# 1_P1.net
KiCad netlist of a schematic drawn in Altium Designer
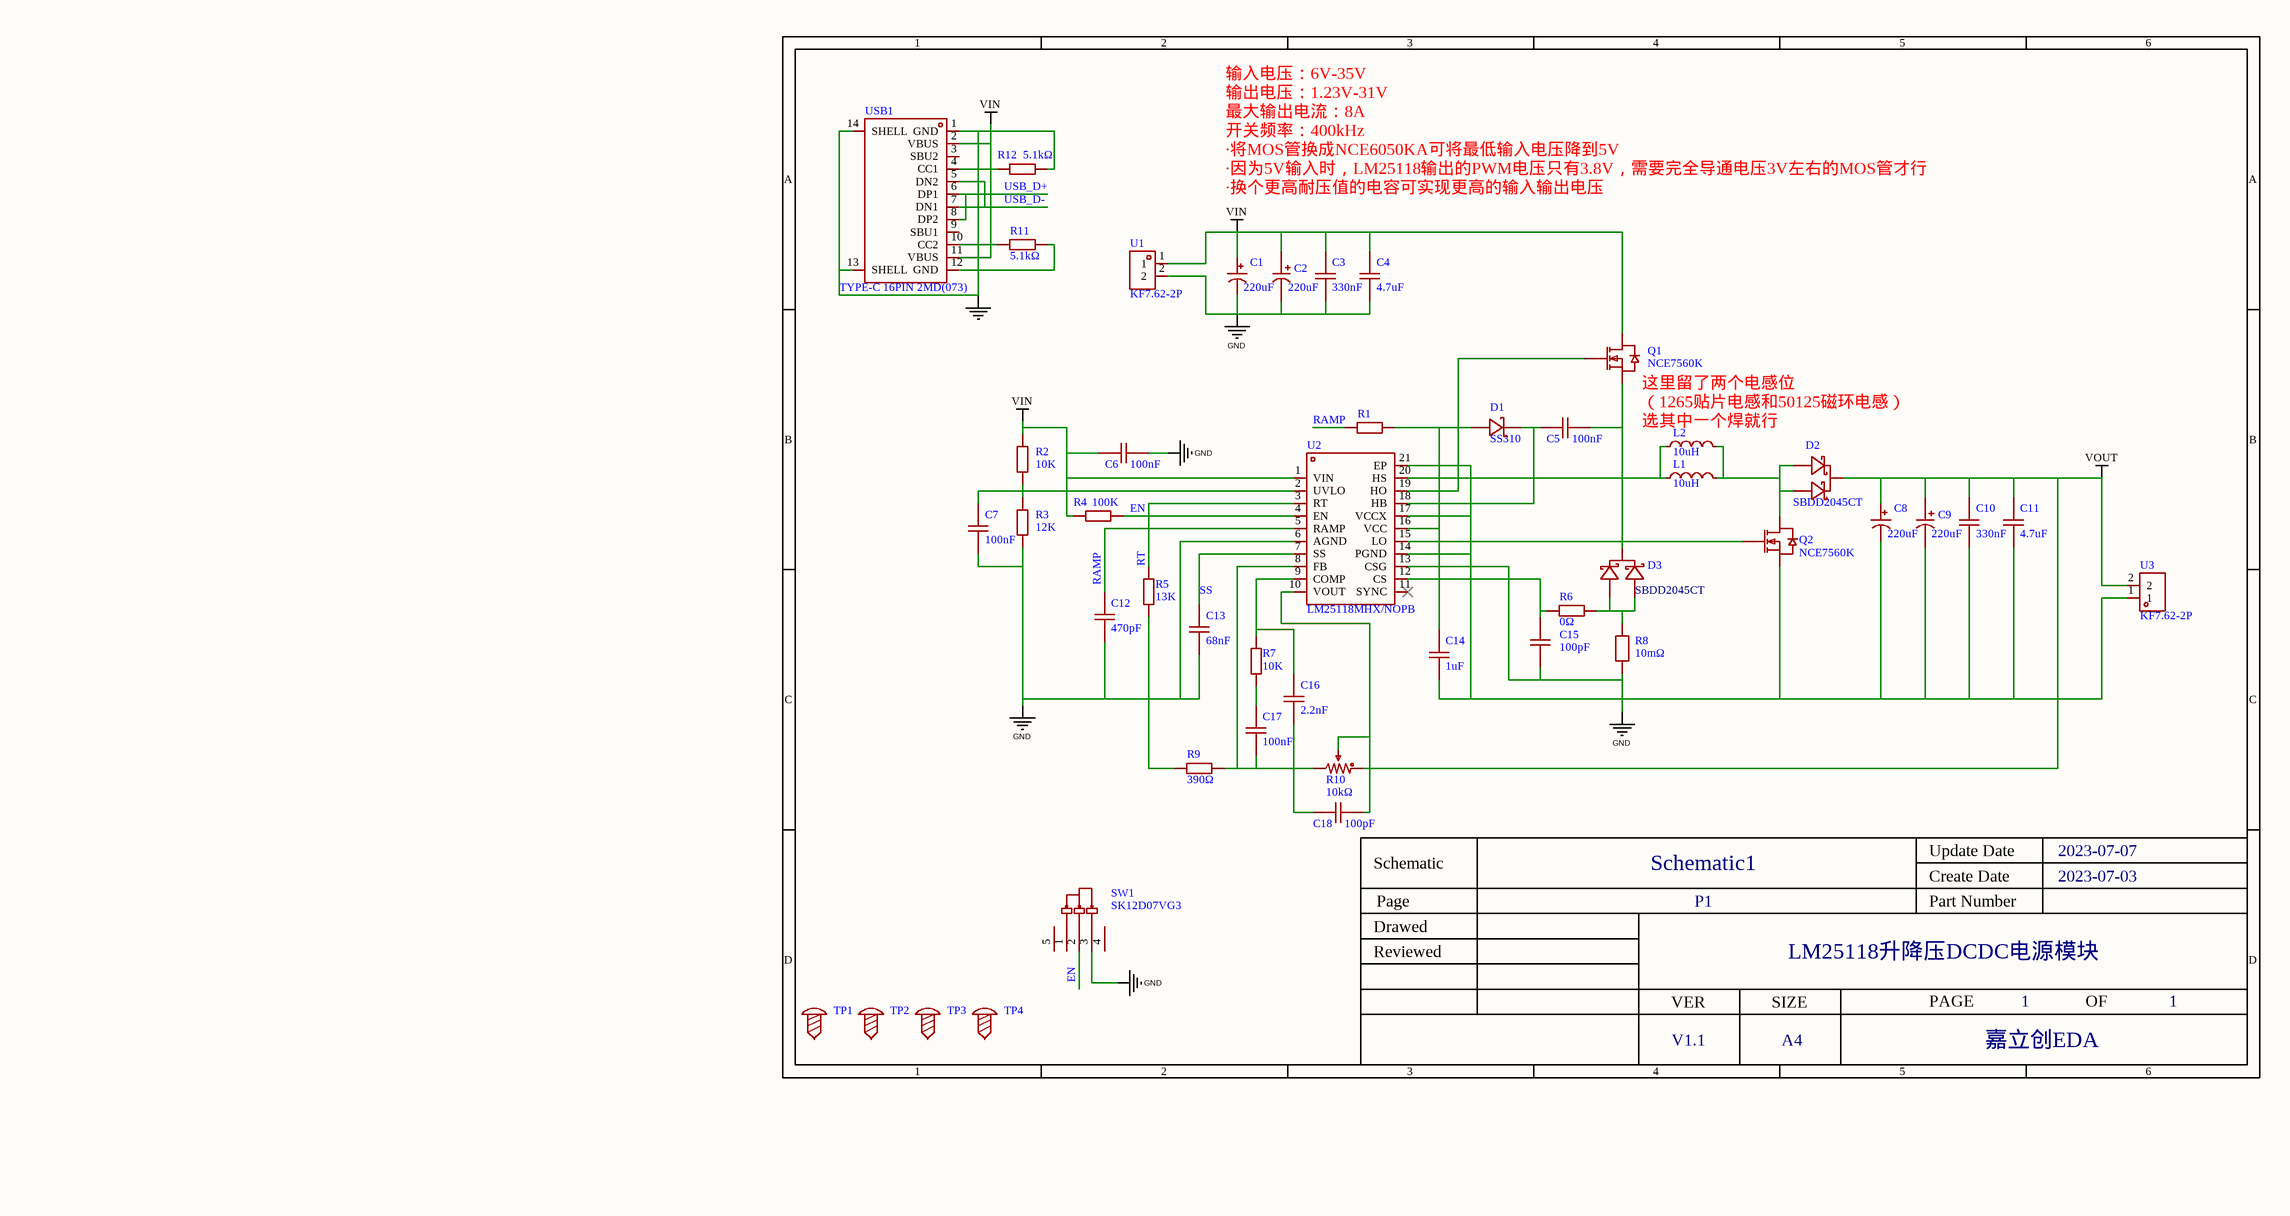
[diagram p0: 1_P1.schdoc]

(export (version "E")
  (design (tool "Eeschema 10.0.6"))
  (components
    (comp (ref "C1")
      (value "220uF")
      (footprint "CAP-TH_BD8.0-P3.50-D0.6-FD")
      (fields
        (field (name "MANUFACTURER") "CX(承兴)")
        (field (name "MANUFACTURER PART") "GR227M035F12RR0VL4FP0")
        (field (name "TOLERANCE") "±20%")
      )
      (libsource (lib "altium-import") (part "root_3_GR227M035F12RR0VL4FP0_"))
    )
    (comp (ref "C2")
      (value "220uF")
      (footprint "CAP-TH_BD8.0-P3.50-D0.6-FD-2")
      (fields
        (field (name "MANUFACTURER") "KNSCHA(科尼盛)")
        (field (name "MANUFACTURER PART") "KNH2220UF35V149EC0049")
        (field (name "TOLERANCE") "±20%")
      )
      (libsource (lib "altium-import") (part "root_3_KNH2220UF35V149EC0049_"))
    )
    (comp (ref "C3")
      (value "330nF")
      (footprint "C0805")
      (libsource (lib "altium-import") (part "root_1_CAP_0805_"))
    )
    (comp (ref "C4")
      (value "4.7uF")
      (footprint "C0805")
      (libsource (lib "altium-import") (part "root_1_CAP_0805_"))
    )
    (comp (ref "C5")
      (value "100nF")
      (footprint "C0805")
      (libsource (lib "altium-import") (part "root_0_CAP_0805_"))
    )
    (comp (ref "C6")
      (value "100nF")
      (footprint "C0805")
      (libsource (lib "altium-import") (part "root_0_CAP_0805_"))
    )
    (comp (ref "C7")
      (value "100nF")
      (footprint "C0805")
      (libsource (lib "altium-import") (part "root_1_CAP_0805_"))
    )
    (comp (ref "C8")
      (value "220uF")
      (footprint "CAP-TH_BD8.0-P3.50-D0.6-FD")
      (fields
        (field (name "MANUFACTURER") "CX(承兴)")
        (field (name "MANUFACTURER PART") "GR227M035F12RR0VL4FP0")
        (field (name "TOLERANCE") "±20%")
      )
      (libsource (lib "altium-import") (part "root_3_GR227M035F12RR0VL4FP0_"))
    )
    (comp (ref "C9")
      (value "220uF")
      (footprint "CAP-TH_BD8.0-P3.50-D0.6-FD-2")
      (fields
        (field (name "MANUFACTURER") "KNSCHA(科尼盛)")
        (field (name "MANUFACTURER PART") "KNH2220UF35V149EC0049")
        (field (name "TOLERANCE") "±20%")
      )
      (libsource (lib "altium-import") (part "root_3_KNH2220UF35V149EC0049_"))
    )
    (comp (ref "C10")
      (value "330nF")
      (footprint "C0805")
      (libsource (lib "altium-import") (part "root_1_CAP_0805_"))
    )
    (comp (ref "C11")
      (value "4.7uF")
      (footprint "C0805")
      (libsource (lib "altium-import") (part "root_1_CAP_0805_"))
    )
    (comp (ref "C12")
      (value "470pF")
      (footprint "C0805")
      (libsource (lib "altium-import") (part "root_1_CAP_0805_"))
    )
    (comp (ref "C13")
      (value "68nF")
      (footprint "C0805")
      (libsource (lib "altium-import") (part "root_1_CAP_0805_"))
    )
    (comp (ref "C14")
      (value "1uF")
      (footprint "C0805")
      (libsource (lib "altium-import") (part "root_1_CAP_0805_"))
    )
    (comp (ref "C15")
      (value "100pF")
      (footprint "C0805")
      (libsource (lib "altium-import") (part "root_1_CAP_0805_"))
    )
    (comp (ref "C16")
      (value "2.2nF")
      (footprint "C0805")
      (libsource (lib "altium-import") (part "root_1_CAP_0805_"))
    )
    (comp (ref "C17")
      (value "100nF")
      (footprint "C0805")
      (libsource (lib "altium-import") (part "root_1_CAP_0805_"))
    )
    (comp (ref "C18")
      (value "100pF")
      (footprint "C0805")
      (libsource (lib "altium-import") (part "root_0_CAP_0805_"))
    )
    (comp (ref "D1")
      (value "SS310")
      (footprint "SMA_L4.3-W2.6-LS5.2-RD")
      (fields (field (name "MANUFACTURER") "MDD"))
      (libsource (lib "altium-import") (part "root_2_SS310_C15874_"))
    )
    (comp (ref "D2")
      (value "SBDD2045CT")
      (footprint "TO-252-2_L6.5-W6.1-P4.58-LS10.0-TL")
      (fields (field (name "MANUFACTURER") "CJ(江苏长电/长晶)"))
      (libsource (lib "altium-import") (part "root_1_SBDD2045CT_"))
    )
    (comp (ref "D3")
      (value "SBDD2045CT")
      (footprint "TO-252-2_L6.5-W6.1-P4.58-LS10.0-TL")
      (fields (field (name "MANUFACTURER") "CJ(江苏长电/长晶)"))
      (libsource (lib "altium-import") (part "root_2_SBDD2045CT_"))
    )
    (comp (ref "L1")
      (value "10uH")
      (footprint "IND-TH_L16.5-W8.5-P11.00-D1.0")
      (fields
        (field (name "MANUFACTURER") "Sunltech(韩国顺磁)")
        (field (name "MANUFACTURER PART") "SLT050125T100MUB")
        (field (name "TOLERANCE") "±20%")
      )
      (libsource (lib "altium-import") (part "root_0_SLT050125T100MUB_"))
    )
    (comp (ref "L2")
      (value "10uH")
      (footprint "IND-SMD_L13.5-W12.6")
      (fields
        (field (name "MANUFACTURER") "XR(祥如)")
        (field (name "MANUFACTURER PART") "XR1265-100M")
        (field (name "TOLERANCE") "±20%")
      )
      (libsource (lib "altium-import") (part "root_0_XR1265-100M_"))
    )
    (comp (ref "Q1")
      (value "NCE7560K")
      (footprint "TO-252-2_L6.6-W6.1-P4.57-LS9.9-TL-CW")
      (fields (field (name "MANUFACTURER") "NCE(无锡新洁能)"))
      (libsource (lib "altium-import") (part "root_0_NCE7560K_"))
    )
    (comp (ref "Q2")
      (value "NCE7560K")
      (footprint "TO-252-2_L6.6-W6.1-P4.57-LS9.9-TL-CW")
      (fields (field (name "MANUFACTURER") "NCE(无锡新洁能)"))
      (libsource (lib "altium-import") (part "root_0_NCE7560K_"))
    )
    (comp (ref "R1")
      (value "100K")
      (footprint "R0805")
      (libsource (lib "altium-import") (part "root_0_Res_0805_"))
    )
    (comp (ref "R2")
      (value "10K")
      (footprint "R0805")
      (libsource (lib "altium-import") (part "root_1_Res_0805_"))
    )
    (comp (ref "R3")
      (value "12K")
      (footprint "R0805")
      (libsource (lib "altium-import") (part "root_1_Res_0805_"))
    )
    (comp (ref "R4")
      (value "100K")
      (footprint "R0805")
      (libsource (lib "altium-import") (part "root_0_Res_0805_"))
    )
    (comp (ref "R5")
      (value "13K")
      (footprint "R0805")
      (libsource (lib "altium-import") (part "root_1_Res_0805_"))
    )
    (comp (ref "R6")
      (value "0Ω")
      (footprint "R0805")
      (libsource (lib "altium-import") (part "root_0_Res_0805_"))
    )
    (comp (ref "R7")
      (value "10K")
      (footprint "R0805")
      (libsource (lib "altium-import") (part "root_1_Res_0805_"))
    )
    (comp (ref "R8")
      (value "10mΩ")
      (footprint "RES-SMD_L6.4-W3.2-R2512")
      (fields
        (field (name "MANUFACTURER") "Milliohm(毫欧)")
        (field (name "MANUFACTURER PART") "HoJLR2512-3W-10mR-1%")
      )
      (libsource (lib "altium-import") (part "root_1_HoJLR2512-3W-10mR-1%_"))
    )
    (comp (ref "R9")
      (value "390Ω")
      (footprint "R0805")
      (libsource (lib "altium-import") (part "root_0_Res_0805_"))
    )
    (comp (ref "R10")
      (value "10kΩ")
      (footprint "RES-ADJ-TH_3P-L10.0-W10.0-P2.50-L")
      (fields
        (field (name "MANUFACTURER") "BOCHEN(博晨)")
        (field (name "MANUFACTURER PART") "3296W-1-103")
        (field (name "TOLERANCE") "±10%")
      )
      (libsource (lib "altium-import") (part "root_0_3296W-1-103_"))
    )
    (comp (ref "R11")
      (value "5.1kΩ")
      (footprint "R0805")
      (fields
        (field (name "MANUFACTURER") "UNI-ROYAL(厚声)")
        (field (name "MANUFACTURER PART") "0805W8F5101T5E")
        (field (name "TOLERANCE") "±1%")
      )
      (libsource (lib "altium-import") (part "root_0_0805W8F5101T5E_"))
    )
    (comp (ref "R12")
      (value "5.1kΩ")
      (footprint "R0805")
      (fields
        (field (name "MANUFACTURER") "UNI-ROYAL(厚声)")
        (field (name "MANUFACTURER PART") "0805W8F5101T5E")
        (field (name "TOLERANCE") "±1%")
      )
      (libsource (lib "altium-import") (part "root_0_0805W8F5101T5E_"))
    )
    (comp (ref "SW1")
      (value "SK12D07VG3")
      (footprint "SW-TH_SK12D07VG3")
      (fields (field (name "MANUFACTURER") "SHOU HAN(首韩)"))
      (libsource (lib "altium-import") (part "root_0_SK12D07VG3_"))
    )
    (comp (ref "TP1") (value "~") (footprint "M3螺丝") (libsource (lib "altium-import") (part "root_0_M3螺丝_")))
    (comp (ref "TP2") (value "~") (footprint "M3螺丝") (libsource (lib "altium-import") (part "root_0_M3螺丝_")))
    (comp (ref "TP3") (value "~") (footprint "M3螺丝") (libsource (lib "altium-import") (part "root_0_M3螺丝_")))
    (comp (ref "TP4") (value "~") (footprint "M3螺丝") (libsource (lib "altium-import") (part "root_0_M3螺丝_")))
    (comp (ref "U1")
      (value "KF7.62-2P")
      (footprint "CONN-TH_2P-P7.62_KEFA_KF7.62-2P")
      (fields (field (name "MANUFACTURER") "KEFA(科发)"))
      (libsource (lib "altium-import") (part "root_0_mirrored_KF7.62-2P_C5173665_"))
    )
    (comp (ref "U2")
      (value "LM25118MHX/NOPB")
      (footprint "HTSSOP-20_L6.5-W4.4-P0.65-LS6.4-BL-EP")
      (fields (field (name "MANUFACTURER") "TI(德州仪器)"))
      (libsource (lib "altium-import") (part "root_0_LM25118MHX/NOPB_"))
    )
    (comp (ref "U3")
      (value "KF7.62-2P")
      (footprint "CONN-TH_2P-P7.62_KEFA_KF7.62-2P")
      (fields (field (name "MANUFACTURER") "KEFA(科发)"))
      (libsource (lib "altium-import") (part "root_2_mirrored_KF7.62-2P_C5173665_"))
    )
    (comp (ref "USB1")
      (value "TYPE-C 16PIN 2MD(073)")
      (footprint "USB-C-SMD_TYPE-C-6PIN-2MD-073")
      (fields (field (name "MANUFACTURER") "SHOU HAN(首韩)"))
      (libsource (lib "altium-import") (part "root_0_mirrored_TYPE-C 16PIN 2MD(073)_"))
    )
  )
  (nets
    (net (code "1") (name "/EN") (class "Default")
      (node (ref "R4") (pin "2") (pinfunction "2_2") (pintype "passive"))
      (node (ref "SW1") (pin "2") (pinfunction "2_2") (pintype "passive"))
      (node (ref "U2") (pin "4") (pinfunction "EN_4") (pintype "passive"))
    )
    (net (code "2") (name "/RAMP") (class "Default")
      (node (ref "C12") (pin "2") (pinfunction "2_2") (pintype "passive"))
      (node (ref "R1") (pin "1") (pinfunction "1_1") (pintype "passive"))
      (node (ref "U2") (pin "5") (pinfunction "RAMP_5") (pintype "passive"))
    )
    (net (code "3") (name "/RT") (class "Default")
      (node (ref "R5") (pin "2") (pinfunction "2_2") (pintype "passive"))
      (node (ref "U2") (pin "3") (pinfunction "RT_3") (pintype "passive"))
    )
    (net (code "4") (name "/SS") (class "Default")
      (node (ref "C13") (pin "2") (pinfunction "2_2") (pintype "passive"))
      (node (ref "U2") (pin "7") (pinfunction "SS_7") (pintype "passive"))
    )
    (net (code "5") (name "/USB_D+") (class "Default")
      (node (ref "USB1") (pin "6") (pinfunction "DP1_6") (pintype "passive"))
      (node (ref "USB1") (pin "8") (pinfunction "DP2_8") (pintype "passive"))
    )
    (net (code "6") (name "/USB_D-") (class "Default")
      (node (ref "USB1") (pin "5") (pinfunction "DN2_5") (pintype "passive"))
      (node (ref "USB1") (pin "7") (pinfunction "DN1_7") (pintype "passive"))
    )
    (net (code "7") (name "GND") (class "Default")
      (node (ref "C1") (pin "2") (pinfunction "2_2") (pintype "passive"))
      (node (ref "C10") (pin "1") (pinfunction "1_1") (pintype "passive"))
      (node (ref "C11") (pin "1") (pinfunction "1_1") (pintype "passive"))
      (node (ref "C12") (pin "1") (pinfunction "1_1") (pintype "passive"))
      (node (ref "C13") (pin "1") (pinfunction "1_1") (pintype "passive"))
      (node (ref "C14") (pin "1") (pinfunction "1_1") (pintype "passive"))
      (node (ref "C15") (pin "1") (pinfunction "1_1") (pintype "passive"))
      (node (ref "C2") (pin "2") (pinfunction "2_2") (pintype "passive"))
      (node (ref "C3") (pin "1") (pinfunction "1_1") (pintype "passive"))
      (node (ref "C4") (pin "1") (pinfunction "1_1") (pintype "passive"))
      (node (ref "C6") (pin "2") (pinfunction "2_2") (pintype "passive"))
      (node (ref "C7") (pin "1") (pinfunction "1_1") (pintype "passive"))
      (node (ref "C8") (pin "2") (pinfunction "2_2") (pintype "passive"))
      (node (ref "C9") (pin "2") (pinfunction "2_2") (pintype "passive"))
      (node (ref "Q2") (pin "3") (pinfunction "S_3") (pintype "passive"))
      (node (ref "R11") (pin "2") (pinfunction "2_2") (pintype "passive"))
      (node (ref "R12") (pin "2") (pinfunction "2_2") (pintype "passive"))
      (node (ref "R3") (pin "1") (pinfunction "1_1") (pintype "passive"))
      (node (ref "R5") (pin "1") (pinfunction "1_1") (pintype "passive"))
      (node (ref "R8") (pin "1") (pinfunction "1_1") (pintype "passive"))
      (node (ref "R9") (pin "1") (pinfunction "1_1") (pintype "passive"))
      (node (ref "SW1") (pin "3") (pinfunction "3_3") (pintype "passive"))
      (node (ref "U1") (pin "2") (pinfunction "2_2") (pintype "passive"))
      (node (ref "U2") (pin "13") (pinfunction "CSG_13") (pintype "passive"))
      (node (ref "U2") (pin "14") (pinfunction "PGND_14") (pintype "passive"))
      (node (ref "U2") (pin "17") (pinfunction "VCCX_17") (pintype "passive"))
      (node (ref "U2") (pin "21") (pinfunction "EP_21") (pintype "passive"))
      (node (ref "U2") (pin "6") (pinfunction "AGND_6") (pintype "passive"))
      (node (ref "U3") (pin "1") (pinfunction "1_1") (pintype "passive"))
      (node (ref "USB1") (pin "1") (pinfunction "GND_1") (pintype "passive"))
      (node (ref "USB1") (pin "12") (pinfunction "GND_12") (pintype "passive"))
      (node (ref "USB1") (pin "13") (pinfunction "SHELL_13") (pintype "passive"))
      (node (ref "USB1") (pin "14") (pinfunction "SHELL_14") (pintype "passive"))
    )
    (net (code "8") (name "Net-(C17-Pad2)") (class "Default")
      (node (ref "C17") (pin "2") (pinfunction "2_2") (pintype "passive"))
      (node (ref "R7") (pin "1") (pinfunction "1_1") (pintype "passive"))
    )
    (net (code "9") (name "Net-(D1-A)") (class "Default")
      (node (ref "C14") (pin "2") (pinfunction "2_2") (pintype "passive"))
      (node (ref "D1") (pin "2") (pinfunction "A_2") (pintype "passive"))
      (node (ref "R1") (pin "2") (pinfunction "2_2") (pintype "passive"))
      (node (ref "U2") (pin "16") (pinfunction "VCC_16") (pintype "passive"))
    )
    (net (code "10") (name "Net-(D1-K)") (class "Default")
      (node (ref "C5") (pin "1") (pinfunction "1_1") (pintype "passive"))
      (node (ref "D1") (pin "1") (pinfunction "K_1") (pintype "passive"))
      (node (ref "U2") (pin "18") (pinfunction "HB_18") (pintype "passive"))
    )
    (net (code "11") (name "Net-(D3-A-Pad1)") (class "Default")
      (node (ref "D3") (pin "1") (pinfunction "A_1") (pintype "passive"))
      (node (ref "D3") (pin "3") (pinfunction "A_3") (pintype "passive"))
      (node (ref "R6") (pin "2") (pinfunction "2_2") (pintype "passive"))
      (node (ref "R8") (pin "2") (pinfunction "2_2") (pintype "passive"))
    )
    (net (code "12") (name "Net-(D3-K)") (class "Default")
      (node (ref "C5") (pin "2") (pinfunction "2_2") (pintype "passive"))
      (node (ref "D3") (pin "4") (pinfunction "K_4") (pintype "passive"))
      (node (ref "L1") (pin "1") (pinfunction "1_1") (pintype "passive"))
      (node (ref "L2") (pin "1") (pinfunction "1_1") (pintype "passive"))
      (node (ref "Q1") (pin "3") (pinfunction "S_3") (pintype "passive"))
      (node (ref "U2") (pin "20") (pinfunction "HS_20") (pintype "passive"))
    )
    (net (code "13") (name "Net-(Q1-G)") (class "Default")
      (node (ref "Q1") (pin "1") (pinfunction "G_1") (pintype "passive"))
      (node (ref "U2") (pin "19") (pinfunction "HO_19") (pintype "passive"))
    )
    (net (code "14") (name "Net-(Q2-D)") (class "Default")
      (node (ref "D2") (pin "1") (pinfunction "A_1") (pintype "passive"))
      (node (ref "D2") (pin "3") (pinfunction "A_3") (pintype "passive"))
      (node (ref "L1") (pin "2") (pinfunction "2_2") (pintype "passive"))
      (node (ref "L2") (pin "2") (pinfunction "2_2") (pintype "passive"))
      (node (ref "Q2") (pin "2") (pinfunction "D_2") (pintype "passive"))
    )
    (net (code "15") (name "Net-(Q2-G)") (class "Default")
      (node (ref "Q2") (pin "1") (pinfunction "G_1") (pintype "passive"))
      (node (ref "U2") (pin "15") (pinfunction "LO_15") (pintype "passive"))
    )
    (net (code "16") (name "Net-(U2-COMP)") (class "Default")
      (node (ref "C16") (pin "2") (pinfunction "2_2") (pintype "passive"))
      (node (ref "R7") (pin "2") (pinfunction "2_2") (pintype "passive"))
      (node (ref "U2") (pin "9") (pinfunction "COMP_9") (pintype "passive"))
    )
    (net (code "17") (name "Net-(U2-CS)") (class "Default")
      (node (ref "C15") (pin "2") (pinfunction "2_2") (pintype "passive"))
      (node (ref "R6") (pin "1") (pinfunction "1_1") (pintype "passive"))
      (node (ref "U2") (pin "12") (pinfunction "CS_12") (pintype "passive"))
    )
    (net (code "18") (name "Net-(U2-FB)") (class "Default")
      (node (ref "C16") (pin "1") (pinfunction "1_1") (pintype "passive"))
      (node (ref "C17") (pin "1") (pinfunction "1_1") (pintype "passive"))
      (node (ref "C18") (pin "1") (pinfunction "1_1") (pintype "passive"))
      (node (ref "R10") (pin "3") (pinfunction "3_3") (pintype "passive"))
      (node (ref "R9") (pin "2") (pinfunction "2_2") (pintype "passive"))
      (node (ref "U2") (pin "8") (pinfunction "FB_8") (pintype "passive"))
    )
    (net (code "19") (name "Net-(U2-UVLO)") (class "Default")
      (node (ref "C7") (pin "2") (pinfunction "2_2") (pintype "passive"))
      (node (ref "R2") (pin "1") (pinfunction "1_1") (pintype "passive"))
      (node (ref "R3") (pin "2") (pinfunction "2_2") (pintype "passive"))
      (node (ref "U2") (pin "2") (pinfunction "UVLO_2") (pintype "passive"))
    )
    (net (code "20") (name "Net-(USB1-CC1)") (class "Default")
      (node (ref "R12") (pin "1") (pinfunction "1_1") (pintype "passive"))
      (node (ref "USB1") (pin "4") (pinfunction "CC1_4") (pintype "passive"))
    )
    (net (code "21") (name "Net-(USB1-CC2)") (class "Default")
      (node (ref "R11") (pin "1") (pinfunction "1_1") (pintype "passive"))
      (node (ref "USB1") (pin "10") (pinfunction "CC2_10") (pintype "passive"))
    )
    (net (code "22") (name "VIN") (class "Default")
      (node (ref "C1") (pin "1") (pinfunction "1_1") (pintype "passive"))
      (node (ref "C2") (pin "1") (pinfunction "1_1") (pintype "passive"))
      (node (ref "C3") (pin "2") (pinfunction "2_2") (pintype "passive"))
      (node (ref "C4") (pin "2") (pinfunction "2_2") (pintype "passive"))
      (node (ref "C6") (pin "1") (pinfunction "1_1") (pintype "passive"))
      (node (ref "Q1") (pin "2") (pinfunction "D_2") (pintype "passive"))
      (node (ref "R2") (pin "2") (pinfunction "2_2") (pintype "passive"))
      (node (ref "R4") (pin "1") (pinfunction "1_1") (pintype "passive"))
      (node (ref "U1") (pin "1") (pinfunction "1_1") (pintype "passive"))
      (node (ref "U2") (pin "1") (pinfunction "VIN_1") (pintype "passive"))
      (node (ref "USB1") (pin "11") (pinfunction "VBUS_11") (pintype "passive"))
      (node (ref "USB1") (pin "2") (pinfunction "VBUS_2") (pintype "passive"))
    )
    (net (code "23") (name "VOUT") (class "Default")
      (node (ref "C10") (pin "2") (pinfunction "2_2") (pintype "passive"))
      (node (ref "C11") (pin "2") (pinfunction "2_2") (pintype "passive"))
      (node (ref "C18") (pin "2") (pinfunction "2_2") (pintype "passive"))
      (node (ref "C8") (pin "1") (pinfunction "1_1") (pintype "passive"))
      (node (ref "C9") (pin "1") (pinfunction "1_1") (pintype "passive"))
      (node (ref "D2") (pin "4") (pinfunction "K_4") (pintype "passive"))
      (node (ref "R10") (pin "1") (pinfunction "1_1") (pintype "passive"))
      (node (ref "R10") (pin "2") (pinfunction "2_2") (pintype "passive"))
      (node (ref "U2") (pin "10") (pinfunction "VOUT_10") (pintype "passive"))
      (node (ref "U3") (pin "2") (pinfunction "2_2") (pintype "passive"))
    )
    (net (code "24") (name "unconnected-(SW1-Pad1)") (class "Default")
      (node (ref "SW1") (pin "1") (pinfunction "1_1") (pintype "passive"))
    )
    (net (code "25") (name "unconnected-(SW1-Pad4)") (class "Default")
      (node (ref "SW1") (pin "4") (pinfunction "4_4") (pintype "passive"))
    )
    (net (code "26") (name "unconnected-(SW1-Pad5)") (class "Default")
      (node (ref "SW1") (pin "5") (pinfunction "5_5") (pintype "passive"))
    )
    (net (code "27") (name "unconnected-(TP1-Pad1)") (class "Default")
      (node (ref "TP1") (pin "1") (pinfunction "1_1") (pintype "passive"))
    )
    (net (code "28") (name "unconnected-(TP2-Pad1)") (class "Default")
      (node (ref "TP2") (pin "1") (pinfunction "1_1") (pintype "passive"))
    )
    (net (code "29") (name "unconnected-(TP3-Pad1)") (class "Default")
      (node (ref "TP3") (pin "1") (pinfunction "1_1") (pintype "passive"))
    )
    (net (code "30") (name "unconnected-(TP4-Pad1)") (class "Default")
      (node (ref "TP4") (pin "1") (pinfunction "1_1") (pintype "passive"))
    )
    (net (code "31") (name "unconnected-(U2-SYNC-Pad11)") (class "Default")
      (node (ref "U2") (pin "11") (pinfunction "SYNC_11") (pintype "passive+no_connect"))
    )
    (net (code "32") (name "unconnected-(USB1-SBU1-Pad9)") (class "Default")
      (node (ref "USB1") (pin "9") (pinfunction "SBU1_9") (pintype "passive"))
    )
    (net (code "33") (name "unconnected-(USB1-SBU2-Pad3)") (class "Default")
      (node (ref "USB1") (pin "3") (pinfunction "SBU2_3") (pintype "passive"))
    )
  )
)
